# Temperature_Sensor_Rev_1.net
KiCad netlist of a schematic drawn in EAGLE
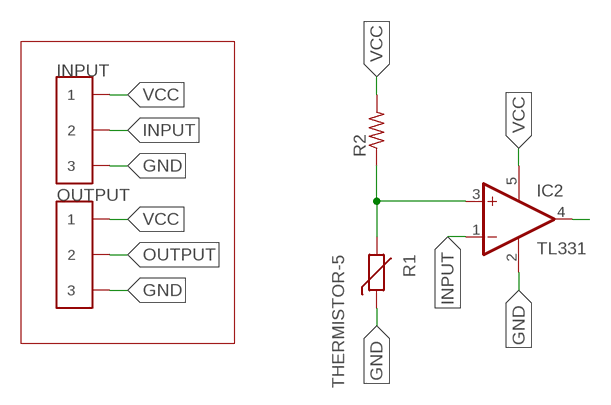
[diagram p0: schematic, sheet 1]

(export (version "E")
  (design (tool "Eeschema 10.0.6"))
  (components
    (comp (ref "IC2")
      (value "TL331")
      (footprint "eagle-import:DBV-R-PDSO-G5")
      (libsource (lib "eagle-import") (part "TL331"))
    )
    (comp (ref "INPUT")
      (value "CONN_3")
      (footprint "eagle-import:CONNECTOR_3")
      (libsource (lib "eagle-import") (part "CONN_3"))
    )
    (comp (ref "OUTPUT")
      (value "CONN_3")
      (footprint "eagle-import:CONNECTOR_3")
      (libsource (lib "eagle-import") (part "CONN_3"))
    )
    (comp (ref "R1")
      (value "THERMISTOR-5")
      (footprint "eagle-import:R-5")
      (libsource (lib "eagle-import") (part "THERMISTOR-5"))
    )
    (comp (ref "R2")
      (value "R-US_R0805")
      (footprint "eagle-import:R0805")
      (libsource (lib "eagle-import") (part "R-US_R0805"))
    )
  )
  (nets
    (net (code "1") (name "GND") (class "Default")
      (node (ref "IC2") (pin "2") (pinfunction "GND_2") (pintype "power_in"))
      (node (ref "INPUT") (pin "5") (pinfunction "3_5") (pintype "bidirectional"))
      (node (ref "INPUT") (pin "6") (pinfunction "3_6") (pintype "bidirectional"))
      (node (ref "OUTPUT") (pin "5") (pinfunction "3_5") (pintype "bidirectional"))
      (node (ref "OUTPUT") (pin "6") (pinfunction "3_6") (pintype "bidirectional"))
      (node (ref "R1") (pin "1") (pinfunction "1_1") (pintype "passive"))
    )
    (net (code "2") (name "INPUT") (class "Default")
      (node (ref "IC2") (pin "1") (pinfunction "-IN_1") (pintype "input"))
      (node (ref "INPUT") (pin "3") (pinfunction "2_3") (pintype "bidirectional"))
      (node (ref "INPUT") (pin "4") (pinfunction "2_4") (pintype "bidirectional"))
    )
    (net (code "3") (name "Net-(IC2-+IN)") (class "Default")
      (node (ref "IC2") (pin "3") (pinfunction "+IN_3") (pintype "input"))
      (node (ref "R1") (pin "2") (pinfunction "2_2") (pintype "passive"))
      (node (ref "R2") (pin "1") (pinfunction "1_1") (pintype "passive"))
    )
    (net (code "4") (name "OUTPUT") (class "Default")
      (node (ref "IC2") (pin "4") (pinfunction "OUT_4") (pintype "output"))
      (node (ref "OUTPUT") (pin "3") (pinfunction "2_3") (pintype "bidirectional"))
      (node (ref "OUTPUT") (pin "4") (pinfunction "2_4") (pintype "bidirectional"))
    )
    (net (code "5") (name "VCC") (class "Default")
      (node (ref "IC2") (pin "5") (pinfunction "V+_5") (pintype "power_in"))
      (node (ref "INPUT") (pin "1") (pinfunction "1_1") (pintype "bidirectional"))
      (node (ref "INPUT") (pin "2") (pinfunction "1_2") (pintype "bidirectional"))
      (node (ref "OUTPUT") (pin "1") (pinfunction "1_1") (pintype "bidirectional"))
      (node (ref "OUTPUT") (pin "2") (pinfunction "1_2") (pintype "bidirectional"))
      (node (ref "R2") (pin "2") (pinfunction "2_2") (pintype "passive"))
    )
  )
)
